# GEARDRONE_F4_4.net
KiCad netlist of a schematic drawn in Altium Designer
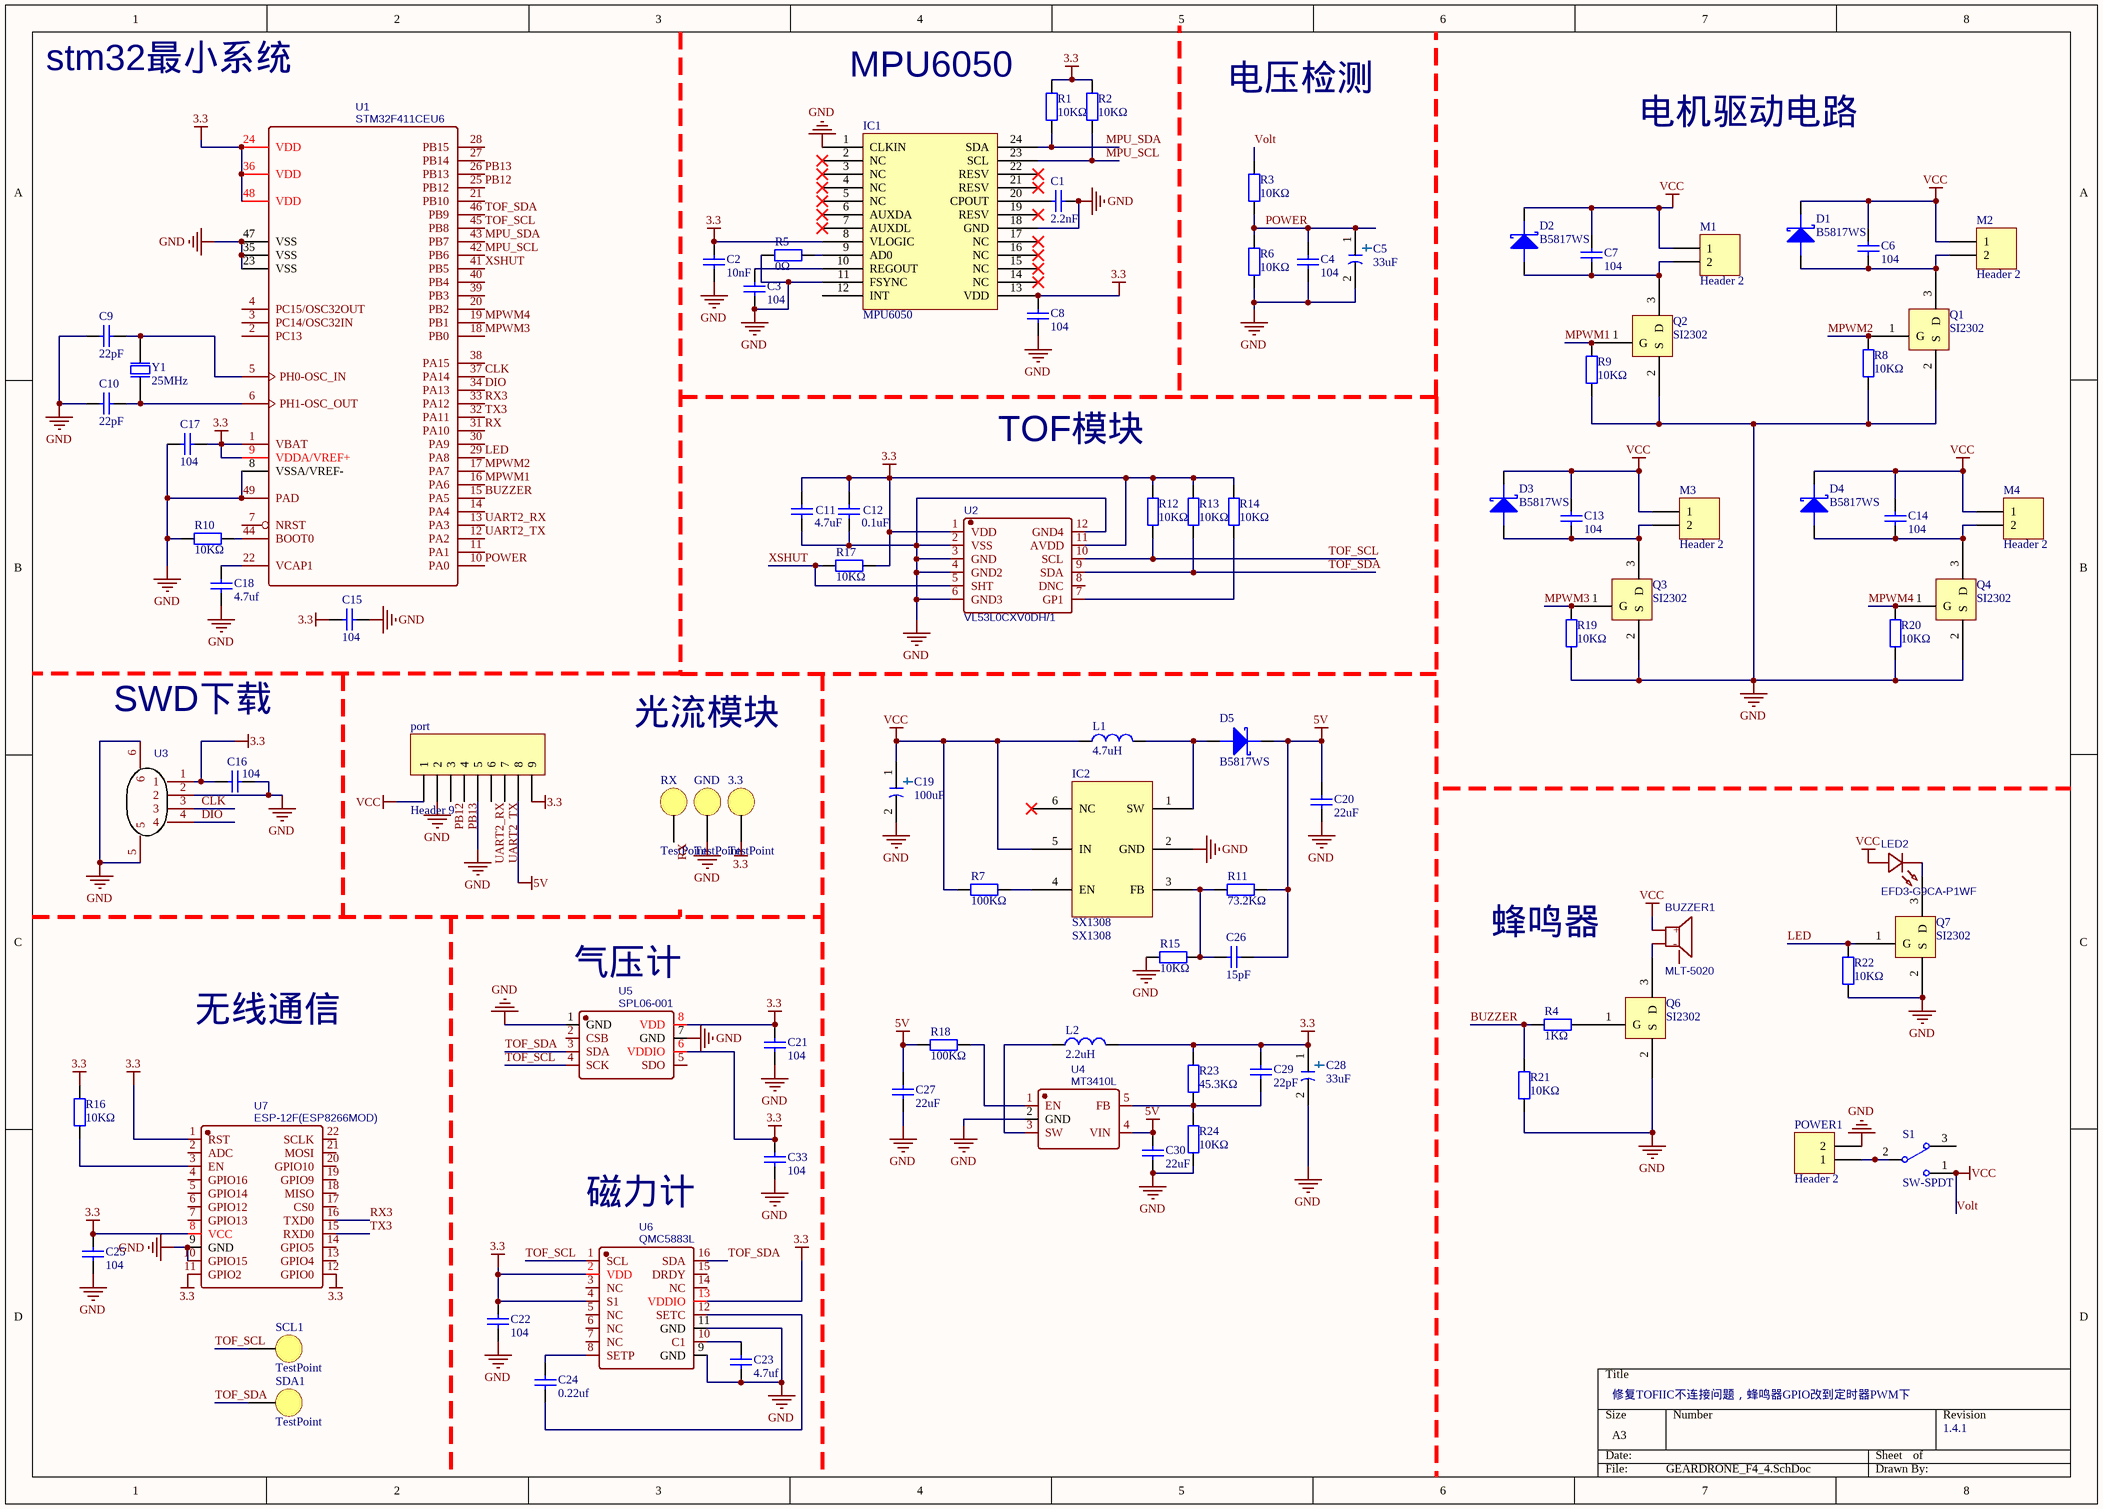
[diagram p0: GEARDRONE_F4_4.SchDoc]

(export (version "E")
  (design (tool "Eeschema 10.0.6"))
  (components
    (comp (ref "3.3")
      (value "TestPoint")
      (footprint "TestPoint")
      (libsource (lib "CQL_SchLib") (part "TestPoint"))
    )
    (comp (ref "BUZZER1")
      (value "MLT-5020")
      (footprint "BUZ-SMD_3P-L5.2-W5.2-P3.50-BR")
      (fields (field (name "BOM_SUPPLIER PART") "C94598"))
      (libsource (lib "Y1") (part "MLT-5020"))
    )
    (comp (ref "C1")
      (value "2.2nF")
      (footprint "0603_C")
      (description "Polarized Capacitor (Radial)")
      (fields (field (name "Comment") "2.2nf") (field (name "PUBLISHER") "Altium Limited"))
      (libsource (lib "电容") (part "Cap Chip 0603"))
    )
    (comp (ref "C2")
      (value "10nF")
      (footprint "0603_C")
      (description "Polarized Capacitor (Radial)")
      (fields (field (name "Comment") "10nf") (field (name "PUBLISHER") "Altium Limited"))
      (libsource (lib "电容") (part "Cap Chip 0603"))
    )
    (comp (ref "C3")
      (value "104")
      (footprint "0603_C")
      (description "Polarized Capacitor (Radial)")
      (fields (field (name "PUBLISHER") "Altium Limited"))
      (libsource (lib "电容") (part "Cap Chip 0603"))
    )
    (comp (ref "C4")
      (value "104")
      (footprint "0603_C")
      (description "Polarized Capacitor (Radial)")
      (fields (field (name "PUBLISHER") "Altium Limited"))
      (libsource (lib "电容") (part "Cap Chip 0603"))
    )
    (comp (ref "C5")
      (value "33uf")
      (footprint "CASE-B_3528")
      (fields (field (name "ALTIUM_UNNAMED_1") "33uF"))
      (libsource (lib "mySchlib") (part "ECAP"))
    )
    (comp (ref "C6")
      (value "104")
      (footprint "0603_C")
      (description "Polarized Capacitor (Radial)")
      (fields (field (name "PUBLISHER") "Altium Limited"))
      (libsource (lib "电容") (part "Cap Chip 0603"))
    )
    (comp (ref "C7")
      (value "104")
      (footprint "0603_C")
      (description "Polarized Capacitor (Radial)")
      (fields (field (name "PUBLISHER") "Altium Limited"))
      (libsource (lib "电容") (part "Cap Chip 0603"))
    )
    (comp (ref "C8")
      (value "104")
      (footprint "0603_C")
      (description "Polarized Capacitor (Radial)")
      (fields (field (name "PUBLISHER") "Altium Limited"))
      (libsource (lib "电容") (part "Cap Chip 0603"))
    )
    (comp (ref "C9")
      (value "22pF")
      (footprint "0603_C")
      (description "Polarized Capacitor (Radial)")
      (fields (field (name "Comment") "22pf") (field (name "PUBLISHER") "Altium Limited"))
      (libsource (lib "电容") (part "Cap Chip 0805"))
    )
    (comp (ref "C10")
      (value "22pF")
      (footprint "0603_C")
      (description "Polarized Capacitor (Radial)")
      (fields (field (name "Comment") "22pf") (field (name "PUBLISHER") "Altium Limited"))
      (libsource (lib "电容") (part "Cap Chip 0805"))
    )
    (comp (ref "C11")
      (value "4.7uF")
      (footprint "0603_C")
      (description "Polarized Capacitor (Radial)")
      (fields (field (name "Comment") "4.7uf") (field (name "PUBLISHER") "Altium Limited"))
      (libsource (lib "电容") (part "Cap Chip 0603"))
    )
    (comp (ref "C12")
      (value "0.1uF")
      (footprint "0603_C")
      (description "Polarized Capacitor (Radial)")
      (fields (field (name "Comment") "0.1uf") (field (name "PUBLISHER") "Altium Limited"))
      (libsource (lib "电容") (part "Cap Chip 0603"))
    )
    (comp (ref "C13")
      (value "104")
      (footprint "0603_C")
      (description "Polarized Capacitor (Radial)")
      (fields (field (name "PUBLISHER") "Altium Limited"))
      (libsource (lib "电容") (part "Cap Chip 0603"))
    )
    (comp (ref "C14")
      (value "104")
      (footprint "0603_C")
      (description "Polarized Capacitor (Radial)")
      (fields (field (name "PUBLISHER") "Altium Limited"))
      (libsource (lib "电容") (part "Cap Chip 0603"))
    )
    (comp (ref "C15")
      (value "104")
      (footprint "0603_C")
      (description "Polarized Capacitor (Radial)")
      (fields (field (name "PUBLISHER") "Altium Limited"))
      (libsource (lib "电容") (part "Cap Chip 0603"))
    )
    (comp (ref "C16")
      (value "104")
      (footprint "0603_C")
      (description "Polarized Capacitor (Radial)")
      (fields (field (name "PUBLISHER") "Altium Limited"))
      (libsource (lib "电容") (part "Cap Chip 0603"))
    )
    (comp (ref "C17")
      (value "104")
      (footprint "0603_C")
      (description "Polarized Capacitor (Radial)")
      (fields (field (name "PUBLISHER") "Altium Limited"))
      (libsource (lib "电容") (part "Cap Chip 0603"))
    )
    (comp (ref "C18")
      (value "4.7uf")
      (footprint "0603_C")
      (description "Polarized Capacitor (Radial)")
      (fields (field (name "PUBLISHER") "Altium Limited"))
      (libsource (lib "电容") (part "Cap Chip 0603"))
    )
    (comp (ref "C19")
      (value "100uf")
      (footprint "CASE-B_3528")
      (fields (field (name "ALTIUM_UNNAMED_1") "100uF"))
      (libsource (lib "mySchlib") (part "ECAP"))
    )
    (comp (ref "C20")
      (value "22uF")
      (footprint "0603_C")
      (description "Polarized Capacitor (Radial)")
      (fields (field (name "Comment") "22uf") (field (name "PUBLISHER") "Altium Limited"))
      (libsource (lib "电容") (part "Cap Chip 0603"))
    )
    (comp (ref "C21")
      (value "104")
      (footprint "0603_C")
      (description "Polarized Capacitor (Radial)")
      (fields (field (name "PUBLISHER") "Altium Limited"))
      (libsource (lib "电容") (part "Cap Chip 0603"))
    )
    (comp (ref "C22")
      (value "104")
      (footprint "0603_C")
      (description "Polarized Capacitor (Radial)")
      (fields (field (name "PUBLISHER") "Altium Limited"))
      (libsource (lib "电容") (part "Cap Chip 0603"))
    )
    (comp (ref "C23")
      (value "4.7uf")
      (footprint "0603_C")
      (description "Polarized Capacitor (Radial)")
      (fields (field (name "PUBLISHER") "Altium Limited"))
      (libsource (lib "电容") (part "Cap Chip 0603"))
    )
    (comp (ref "C24")
      (value "0.22uf")
      (footprint "0603_C")
      (description "Polarized Capacitor (Radial)")
      (fields (field (name "PUBLISHER") "Altium Limited"))
      (libsource (lib "电容") (part "Cap Chip 0603"))
    )
    (comp (ref "C25")
      (value "104")
      (footprint "0603_C")
      (description "Polarized Capacitor (Radial)")
      (fields (field (name "PUBLISHER") "Altium Limited"))
      (libsource (lib "电容") (part "Cap Chip 0603"))
    )
    (comp (ref "C26")
      (value "15pF")
      (footprint "0603_C")
      (description "Polarized Capacitor (Radial)")
      (fields (field (name "Comment") "15pf") (field (name "PUBLISHER") "Altium Limited"))
      (libsource (lib "电容") (part "Cap Chip 0603"))
    )
    (comp (ref "C27")
      (value "22uF")
      (footprint "0603_C")
      (description "Polarized Capacitor (Radial)")
      (fields (field (name "PUBLISHER") "Altium Limited"))
      (libsource (lib "电容") (part "Cap Chip 0603"))
    )
    (comp (ref "C28")
      (value "33uf")
      (footprint "CASE-B_3528")
      (fields (field (name "ALTIUM_UNNAMED_1") "33uF"))
      (libsource (lib "mySchlib") (part "ECAP"))
    )
    (comp (ref "C29")
      (value "22pF")
      (footprint "0603_C")
      (description "Polarized Capacitor (Radial)")
      (fields (field (name "PUBLISHER") "Altium Limited"))
      (libsource (lib "电容") (part "Cap Chip 0603"))
    )
    (comp (ref "C30")
      (value "22uF")
      (footprint "0603_C")
      (description "Polarized Capacitor (Radial)")
      (fields (field (name "PUBLISHER") "Altium Limited"))
      (libsource (lib "电容") (part "Cap Chip 0603"))
    )
    (comp (ref "C33")
      (value "104")
      (footprint "0603_C")
      (description "Polarized Capacitor (Radial)")
      (fields (field (name "PUBLISHER") "Altium Limited"))
      (libsource (lib "电容") (part "Cap Chip 0603"))
    )
    (comp (ref "D1")
      (value "B5817WS")
      (footprint "SOD-323")
      (libsource (lib "二极管 三极管 MOS") (part "DIODE-TVS"))
    )
    (comp (ref "D2")
      (value "B5817WS")
      (footprint "SOD-323")
      (libsource (lib "二极管 三极管 MOS") (part "DIODE-TVS"))
    )
    (comp (ref "D3")
      (value "B5817WS")
      (footprint "SOD-323")
      (libsource (lib "二极管 三极管 MOS") (part "DIODE-TVS"))
    )
    (comp (ref "D4")
      (value "B5817WS")
      (footprint "SOD-323")
      (libsource (lib "二极管 三极管 MOS") (part "DIODE-TVS"))
    )
    (comp (ref "D5")
      (value "B5817WS")
      (footprint "SOD-323")
      (libsource (lib "二极管 三极管 MOS") (part "DIODE-TVS"))
    )
    (comp (ref "GND")
      (value "TestPoint")
      (footprint "TestPoint")
      (libsource (lib "CQL_SchLib") (part "TestPoint"))
    )
    (comp (ref "IC1")
      (value "MPU6050")
      (footprint "LC-QFN-24_4x4x05P")
      (description "三轴陀螺仪")
      (libsource (lib "模块") (part "MPU6050"))
    )
    (comp (ref "IC2") (value "SX1308") (footprint "LC-SOT-23-6") (libsource (lib "Schlib1") (part "SX1308")))
    (comp (ref "L1")
      (value "4.7uH")
      (footprint "CD43NP")
      (description "Inductor")
      (fields (field (name "PUBLISHER") "Altium Limited"))
      (libsource (lib "电感磁珠共轭圈") (part "Inductor Chip"))
    )
    (comp (ref "L2")
      (value "2.2uH")
      (footprint "IND-SMD_L3.0-W3.0")
      (description "Inductor")
      (fields (field (name "PUBLISHER") "Altium Limited"))
      (libsource (lib "电感磁珠共轭圈") (part "Inductor Chip"))
    )
    (comp (ref "LED2")
      (value "EFD3-G9CA-P1WF")
      (footprint "LED3528")
      (fields (field (name "BOM_SUPPLIER PART") "C507038") (field (name "CONTRIBUTOR") "LCSC"))
      (libsource (lib "altium-import") (part "root_2_EFD3-G9CA-P1WF_"))
    )
    (comp (ref "M1")
      (value "Header 2")
      (footprint "HDR1X2")
      (description "Header, 2-Pin")
      (fields (field (name "PUBLISHER") "Altium Limited"))
      (libsource (lib "The BeatlesIntegratedLibrary") (part "Header 2"))
    )
    (comp (ref "M2")
      (value "Header 2")
      (footprint "HDR1X2")
      (description "Header, 2-Pin")
      (fields (field (name "PUBLISHER") "Altium Limited"))
      (libsource (lib "The BeatlesIntegratedLibrary") (part "Header 2"))
    )
    (comp (ref "M3")
      (value "Header 2")
      (footprint "HDR1X2")
      (description "Header, 2-Pin")
      (fields (field (name "PUBLISHER") "Altium Limited"))
      (libsource (lib "The BeatlesIntegratedLibrary") (part "Header 2"))
    )
    (comp (ref "M4")
      (value "Header 2")
      (footprint "HDR1X2")
      (description "Header, 2-Pin")
      (fields (field (name "PUBLISHER") "Altium Limited"))
      (libsource (lib "The BeatlesIntegratedLibrary") (part "Header 2"))
    )
    (comp (ref "port")
      (value "Header 9")
      (footprint "HDR1X9")
      (description "Header, 9-Pin")
      (fields (field (name "PUBLISHER") "Altium Limited"))
      (libsource (lib "Miscellaneous Connectors") (part "Header 9"))
    )
    (comp (ref "POWER1")
      (value "Header 2")
      (footprint "HDR1X2")
      (description "Header, 2-Pin")
      (fields (field (name "PUBLISHER") "Altium Limited"))
      (libsource (lib "") (part "Header 2_1"))
    )
    (comp (ref "Q1")
      (value "SI2302")
      (footprint "LC-SOT-23(SOT-23-3)")
      (libsource (lib "SI2302") (part "HANDSOME-SI2302-N"))
    )
    (comp (ref "Q2")
      (value "SI2302")
      (footprint "LC-SOT-23(SOT-23-3)")
      (libsource (lib "SI2302") (part "HANDSOME-SI2302-N"))
    )
    (comp (ref "Q3")
      (value "SI2302")
      (footprint "LC-SOT-23(SOT-23-3)")
      (libsource (lib "SI2302") (part "HANDSOME-SI2302-N"))
    )
    (comp (ref "Q4")
      (value "SI2302")
      (footprint "LC-SOT-23(SOT-23-3)")
      (libsource (lib "SI2302") (part "HANDSOME-SI2302-N"))
    )
    (comp (ref "Q6")
      (value "SI2302")
      (footprint "LC-SOT-23(SOT-23-3)")
      (libsource (lib "SI2302") (part "HANDSOME-SI2302-N"))
    )
    (comp (ref "Q7")
      (value "SI2302")
      (footprint "LC-SOT-23(SOT-23-3)")
      (libsource (lib "SI2302") (part "HANDSOME-SI2302-N"))
    )
    (comp (ref "R1")
      (value "10KΩ")
      (footprint "0603_R")
      (description "Resistor")
      (fields (field (name "Comment") "10k") (field (name "PUBLISHER") "Altium Limited"))
      (libsource (lib "电阻") (part "Resistor Chip 0805"))
    )
    (comp (ref "R2")
      (value "10KΩ")
      (footprint "0603_R")
      (description "Resistor")
      (fields (field (name "Comment") "10k") (field (name "PUBLISHER") "Altium Limited"))
      (libsource (lib "电阻") (part "Resistor Chip 0805"))
    )
    (comp (ref "R3")
      (value "10KΩ")
      (footprint "0603_R")
      (description "Resistor")
      (fields (field (name "Comment") "10k") (field (name "PUBLISHER") "Altium Limited"))
      (libsource (lib "电阻") (part "Resistor Chip 0805"))
    )
    (comp (ref "R4")
      (value "1KΩ")
      (footprint "0603_R")
      (description "Resistor")
      (fields (field (name "Comment") "1k") (field (name "PUBLISHER") "Altium Limited"))
      (libsource (lib "") (part "Resistor Chip 0805_3"))
    )
    (comp (ref "R5")
      (value "0Ω")
      (footprint "0603_R")
      (description "Resistor")
      (fields (field (name "Comment") "0") (field (name "PUBLISHER") "Altium Limited"))
      (libsource (lib "") (part "Resistor Chip 0805_1"))
    )
    (comp (ref "R6")
      (value "10KΩ")
      (footprint "0603_R")
      (description "Resistor")
      (fields (field (name "Comment") "10k") (field (name "PUBLISHER") "Altium Limited"))
      (libsource (lib "电阻") (part "Resistor Chip 0805"))
    )
    (comp (ref "R7")
      (value "100KΩ")
      (footprint "0603_R")
      (description "Resistor")
      (fields (field (name "Comment") "100k") (field (name "PUBLISHER") "Altium Limited"))
      (libsource (lib "") (part "Resistor Chip 0805_1"))
    )
    (comp (ref "R8")
      (value "10KΩ")
      (footprint "0603_R")
      (description "Resistor")
      (fields (field (name "Comment") "10k") (field (name "PUBLISHER") "Altium Limited"))
      (libsource (lib "电阻") (part "Resistor Chip 0805"))
    )
    (comp (ref "R9")
      (value "10KΩ")
      (footprint "0603_R")
      (description "Resistor")
      (fields (field (name "Comment") "10k") (field (name "PUBLISHER") "Altium Limited"))
      (libsource (lib "") (part "Resistor Chip 0805_2"))
    )
    (comp (ref "R10")
      (value "10KΩ")
      (footprint "0603_R")
      (description "Resistor")
      (fields (field (name "Comment") "10kΩ") (field (name "PUBLISHER") "Altium Limited"))
      (libsource (lib "") (part "Resistor Chip 0805_1"))
    )
    (comp (ref "R11")
      (value "73.2KΩ")
      (footprint "0603_R")
      (description "Resistor")
      (fields (field (name "Comment") "73.2k") (field (name "PUBLISHER") "Altium Limited"))
      (libsource (lib "") (part "Resistor Chip 0805_1"))
    )
    (comp (ref "R12")
      (value "10KΩ")
      (footprint "0603_R")
      (description "Resistor")
      (fields (field (name "Comment") "10k") (field (name "PUBLISHER") "Altium Limited"))
      (libsource (lib "电阻") (part "Resistor Chip 0805"))
    )
    (comp (ref "R13")
      (value "10KΩ")
      (footprint "0603_R")
      (description "Resistor")
      (fields (field (name "Comment") "10k") (field (name "PUBLISHER") "Altium Limited"))
      (libsource (lib "电阻") (part "Resistor Chip 0805"))
    )
    (comp (ref "R14")
      (value "10KΩ")
      (footprint "0603_R")
      (description "Resistor")
      (fields (field (name "Comment") "10k") (field (name "PUBLISHER") "Altium Limited"))
      (libsource (lib "电阻") (part "Resistor Chip 0805"))
    )
    (comp (ref "R15")
      (value "10KΩ")
      (footprint "0603_R")
      (description "Resistor")
      (fields (field (name "Comment") "10k") (field (name "PUBLISHER") "Altium Limited"))
      (libsource (lib "") (part "Resistor Chip 0805_3"))
    )
    (comp (ref "R16")
      (value "10KΩ")
      (footprint "0603_R")
      (description "Resistor")
      (fields (field (name "Comment") "10k") (field (name "PUBLISHER") "Altium Limited"))
      (libsource (lib "电阻") (part "Resistor Chip 0805"))
    )
    (comp (ref "R17")
      (value "10KΩ")
      (footprint "0603_R")
      (description "Resistor")
      (fields (field (name "Comment") "10k") (field (name "PUBLISHER") "Altium Limited"))
      (libsource (lib "") (part "Resistor Chip 0805_1"))
    )
    (comp (ref "R18")
      (value "100KΩ")
      (footprint "0603_R")
      (description "Resistor")
      (fields (field (name "Comment") "100k") (field (name "PUBLISHER") "Altium Limited"))
      (libsource (lib "") (part "Resistor Chip 0805_1"))
    )
    (comp (ref "R19")
      (value "10KΩ")
      (footprint "0603_R")
      (description "Resistor")
      (fields (field (name "Comment") "10k") (field (name "PUBLISHER") "Altium Limited"))
      (libsource (lib "电阻") (part "Resistor Chip 0805"))
    )
    (comp (ref "R20")
      (value "10KΩ")
      (footprint "0603_R")
      (description "Resistor")
      (fields (field (name "Comment") "10k") (field (name "PUBLISHER") "Altium Limited"))
      (libsource (lib "电阻") (part "Resistor Chip 0805"))
    )
    (comp (ref "R21")
      (value "10KΩ")
      (footprint "0603_R")
      (description "Resistor")
      (fields (field (name "Comment") "10k") (field (name "PUBLISHER") "Altium Limited"))
      (libsource (lib "") (part "Resistor Chip 0805_2"))
    )
    (comp (ref "R22")
      (value "10KΩ")
      (footprint "0603_R")
      (description "Resistor")
      (fields (field (name "Comment") "10k") (field (name "PUBLISHER") "Altium Limited"))
      (libsource (lib "") (part "Resistor Chip 0805_2"))
    )
    (comp (ref "R23")
      (value "45.3KΩ")
      (footprint "0603_R")
      (description "Resistor")
      (fields (field (name "PUBLISHER") "Altium Limited"))
      (libsource (lib "") (part "Resistor Chip 0805_2"))
    )
    (comp (ref "R24")
      (value "10KΩ")
      (footprint "0603_R")
      (description "Resistor")
      (fields (field (name "PUBLISHER") "Altium Limited"))
      (libsource (lib "") (part "Resistor Chip 0805_2"))
    )
    (comp (ref "RX")
      (value "TestPoint")
      (footprint "TestPoint")
      (libsource (lib "CQL_SchLib") (part "TestPoint"))
    )
    (comp (ref "S1")
      (value "SW-SPDT")
      (footprint "8.5*3.5_3P")
      (description "SPDT Subminiature Toggle Switch, Right Angle Mounting, Vertical Actuation")
      (fields (field (name "PUBLISHER") "Altium Limited"))
      (libsource (lib "开关按键器件") (part "SW-SPDT"))
    )
    (comp (ref "SCL1")
      (value "TestPoint")
      (footprint "TestPoint")
      (libsource (lib "CQL_SchLib") (part "TestPoint"))
    )
    (comp (ref "SDA1")
      (value "TestPoint")
      (footprint "TestPoint")
      (libsource (lib "CQL_SchLib") (part "TestPoint"))
    )
    (comp (ref "U1")
      (value "STM32F411CEU6")
      (footprint "UFQFPN-48_L7.0-W7.0-P0.50-BL-EP")
      (fields (field (name "BOM_SUPPLIER PART") "C60420"))
      (libsource (lib "altium-import") (part "root_0_STM32F411CEU6_"))
    )
    (comp (ref "U2")
      (value "VL53L0CXV0DH/1")
      (footprint "OPTO-SMD_12P_VL53L0CXV0DH-1")
      (fields (field (name "BOM_SUPPLIER PART") "C91199"))
      (libsource (lib "Y1") (part "VL53L0CXV0DH/1"))
    )
    (comp (ref "U3")
      (value "SM04B-GHS-TB(LF)(SN)")
      (footprint "CONN-SMD_4P-P1.25_SM04B-GHS-TB-LF-SN")
      (fields (field (name "BOM_SUPPLIER PART") "C189895") (field (name "CONTRIBUTOR") "LCSC"))
      (libsource (lib "Y1") (part "SM04B-GHS-TB(LF)(SN)"))
    )
    (comp (ref "U4")
      (value "MT3410L")
      (footprint "SOT-23-5_L2.9-W1.6-P0.95-LS2.8-BL")
      (fields (field (name "BOM_SUPPLIER PART") "C83223"))
      (libsource (lib "altium-import") (part "root_0_MT3410L_"))
    )
    (comp (ref "U5")
      (value "SPL06-001")
      (footprint "SENSOR-SMD_SPL06-001")
      (fields (field (name "BOM_SUPPLIER PART") "C2684428") (field (name "CONTRIBUTOR") "LCSC"))
      (libsource (lib "altium-import") (part "root_0_SPL06-001_"))
    )
    (comp (ref "U6")
      (value "QMC5883L")
      (footprint "LPCC-16_L3.0-W3.0-P0.50-BL")
      (fields
        (field (name "BOM_SUPPLIER PART") "C2859540")
        (field (name "BOM_MANUFACTURER PART") "HMC5883L")
        (field (name "CONTRIBUTOR") "LCSC")
      )
      (libsource (lib "altium-import") (part "root_0_HMC5883L_"))
    )
    (comp (ref "U7")
      (value "ESP-12F(ESP8266MOD)")
      (footprint "WIFIM-SMD_ESP-12F-ESP8266MOD")
      (fields (field (name "BOM_SUPPLIER PART") "C82891"))
      (libsource (lib "altium-import") (part "root_0_ESP-12F(ESP8266MOD)_"))
    )
    (comp (ref "Y1")
      (value "25MHZ 5032")
      (footprint "SMD-5032_2P")
      (description "Crystal Oscillator")
      (fields (field (name "FREQUENCY") "25MHz") (field (name "PUBLISHER") "Altium Limited"))
      (libsource (lib "蜂鸣器 咪头 保险丝 电池 晶振") (part "XTAL"))
    )
  )
  (nets
    (net (code "1") (name "/BUZZER") (class "Default")
      (node (ref "R21") (pin "2") (pinfunction "2_2") (pintype "passive"))
      (node (ref "R4") (pin "2") (pinfunction "2_2") (pintype "passive"))
      (node (ref "U1") (pin "15") (pinfunction "PA5_15") (pintype "passive"))
    )
    (net (code "2") (name "/CLK") (class "Default")
      (node (ref "U1") (pin "37") (pinfunction "PA14_37") (pintype "passive"))
      (node (ref "U3") (pin "3") (pinfunction "3_3") (pintype "passive"))
    )
    (net (code "3") (name "/DIO") (class "Default")
      (node (ref "U1") (pin "34") (pinfunction "PA13_34") (pintype "passive"))
      (node (ref "U3") (pin "4") (pinfunction "4_4") (pintype "passive"))
    )
    (net (code "4") (name "/LED") (class "Default")
      (node (ref "Q7") (pin "1") (pinfunction "G_1") (pintype "passive"))
      (node (ref "R22") (pin "2") (pinfunction "2_2") (pintype "passive"))
      (node (ref "U1") (pin "29") (pinfunction "PA8_29") (pintype "passive"))
    )
    (net (code "5") (name "/MPU_SCL") (class "Default")
      (node (ref "IC1") (pin "23") (pinfunction "SCL_23") (pintype "passive"))
      (node (ref "R2") (pin "2") (pinfunction "2_2") (pintype "passive"))
      (node (ref "U1") (pin "42") (pinfunction "PB6_42") (pintype "passive"))
    )
    (net (code "6") (name "/MPU_SDA") (class "Default")
      (node (ref "IC1") (pin "24") (pinfunction "SDA_24") (pintype "passive"))
      (node (ref "R1") (pin "2") (pinfunction "2_2") (pintype "passive"))
      (node (ref "U1") (pin "43") (pinfunction "PB7_43") (pintype "passive"))
    )
    (net (code "7") (name "/MPWM1") (class "Default")
      (node (ref "Q2") (pin "1") (pinfunction "G_1") (pintype "passive"))
      (node (ref "R9") (pin "2") (pinfunction "2_2") (pintype "passive"))
      (node (ref "U1") (pin "16") (pinfunction "PA6_16") (pintype "passive"))
    )
    (net (code "8") (name "/MPWM2") (class "Default")
      (node (ref "Q1") (pin "1") (pinfunction "G_1") (pintype "passive"))
      (node (ref "R8") (pin "1") (pinfunction "1_1") (pintype "passive"))
      (node (ref "U1") (pin "17") (pinfunction "PA7_17") (pintype "passive"))
    )
    (net (code "9") (name "/MPWM3") (class "Default")
      (node (ref "Q3") (pin "1") (pinfunction "G_1") (pintype "passive"))
      (node (ref "R19") (pin "1") (pinfunction "1_1") (pintype "passive"))
      (node (ref "U1") (pin "18") (pinfunction "PB0_18") (pintype "passive"))
    )
    (net (code "10") (name "/MPWM4") (class "Default")
      (node (ref "Q4") (pin "1") (pinfunction "G_1") (pintype "passive"))
      (node (ref "R20") (pin "1") (pinfunction "1_1") (pintype "passive"))
      (node (ref "U1") (pin "19") (pinfunction "PB1_19") (pintype "passive"))
    )
    (net (code "11") (name "/PB12") (class "Default")
      (node (ref "U1") (pin "25") (pinfunction "PB12_25") (pintype "passive"))
      (node (ref "port") (pin "3") (pinfunction "3_3") (pintype "passive"))
    )
    (net (code "12") (name "/PB13") (class "Default")
      (node (ref "U1") (pin "26") (pinfunction "PB13_26") (pintype "passive"))
      (node (ref "port") (pin "4") (pinfunction "4_4") (pintype "passive"))
    )
    (net (code "13") (name "/POWER") (class "Default")
      (node (ref "C4") (pin "1") (pinfunction "1_1") (pintype "passive"))
      (node (ref "C5") (pin "1") (pinfunction "1_1") (pintype "passive"))
      (node (ref "R3") (pin "2") (pinfunction "2_2") (pintype "passive"))
      (node (ref "R6") (pin "1") (pinfunction "1_1") (pintype "passive"))
      (node (ref "U1") (pin "10") (pinfunction "PA0_10") (pintype "passive"))
    )
    (net (code "14") (name "/RX") (class "Default")
      (node (ref "RX") (pin "1") (pinfunction "TestPoint_1") (pintype "passive"))
      (node (ref "U1") (pin "31") (pinfunction "PA10_31") (pintype "passive"))
    )
    (net (code "15") (name "/RX3") (class "Default")
      (node (ref "U1") (pin "33") (pinfunction "PA12_33") (pintype "passive"))
      (node (ref "U7") (pin "16") (pinfunction "TXD0_16") (pintype "passive"))
    )
    (net (code "16") (name "/TOF_SCL") (class "Default")
      (node (ref "R12") (pin "2") (pinfunction "2_2") (pintype "passive"))
      (node (ref "SCL1") (pin "1") (pinfunction "TestPoint_1") (pintype "passive"))
      (node (ref "U1") (pin "45") (pinfunction "PB8_45") (pintype "passive"))
      (node (ref "U2") (pin "10") (pinfunction "SCL_10") (pintype "passive"))
      (node (ref "U5") (pin "4") (pinfunction "SCK_4") (pintype "passive"))
      (node (ref "U6") (pin "1") (pinfunction "SCL_1") (pintype "passive"))
    )
    (net (code "17") (name "/TOF_SDA") (class "Default")
      (node (ref "R13") (pin "2") (pinfunction "2_2") (pintype "passive"))
      (node (ref "SDA1") (pin "1") (pinfunction "TestPoint_1") (pintype "passive"))
      (node (ref "U1") (pin "46") (pinfunction "PB9_46") (pintype "passive"))
      (node (ref "U2") (pin "9") (pinfunction "SDA_9") (pintype "passive"))
      (node (ref "U5") (pin "3") (pinfunction "SDA_3") (pintype "passive"))
      (node (ref "U6") (pin "16") (pinfunction "SDA_16") (pintype "passive"))
    )
    (net (code "18") (name "/TX3") (class "Default")
      (node (ref "U1") (pin "32") (pinfunction "PA11_32") (pintype "passive"))
      (node (ref "U7") (pin "15") (pinfunction "RXD0_15") (pintype "passive"))
    )
    (net (code "19") (name "/UART2_RX") (class "Default")
      (node (ref "U1") (pin "13") (pinfunction "PA3_13") (pintype "passive"))
      (node (ref "port") (pin "6") (pinfunction "6_6") (pintype "passive"))
    )
    (net (code "20") (name "/UART2_TX") (class "Default")
      (node (ref "U1") (pin "12") (pinfunction "PA2_12") (pintype "passive"))
      (node (ref "port") (pin "7") (pinfunction "7_7") (pintype "passive"))
    )
    (net (code "21") (name "/XSHUT") (class "Default")
      (node (ref "R17") (pin "1") (pinfunction "1_1") (pintype "passive"))
      (node (ref "U1") (pin "41") (pinfunction "PB5_41") (pintype "passive"))
      (node (ref "U2") (pin "5") (pinfunction "SHT_5") (pintype "passive"))
    )
    (net (code "22") (name "3.3") (class "Default")
      (node (ref "3.3") (pin "1") (pinfunction "TestPoint_1") (pintype "passive"))
      (node (ref "C11") (pin "2") (pinfunction "2_2") (pintype "passive"))
      (node (ref "C12") (pin "2") (pinfunction "2_2") (pintype "passive"))
      (node (ref "C15") (pin "2") (pinfunction "2_2") (pintype "passive"))
      (node (ref "C16") (pin "2") (pinfunction "2_2") (pintype "passive"))
      (node (ref "C17") (pin "1") (pinfunction "1_1") (pintype "passive"))
      (node (ref "C2") (pin "2") (pinfunction "2_2") (pintype "passive"))
      (node (ref "C21") (pin "1") (pinfunction "1_1") (pintype "passive"))
      (node (ref "C22") (pin "1") (pinfunction "1_1") (pintype "passive"))
      (node (ref "C25") (pin "1") (pinfunction "1_1") (pintype "passive"))
      (node (ref "C28") (pin "1") (pinfunction "1_1") (pintype "passive"))
      (node (ref "C29") (pin "1") (pinfunction "1_1") (pintype "passive"))
      (node (ref "C33") (pin "1") (pinfunction "1_1") (pintype "passive"))
      (node (ref "C8") (pin "1") (pinfunction "1_1") (pintype "passive"))
      (node (ref "IC1") (pin "13") (pinfunction "VDD_13") (pintype "passive"))
      (node (ref "IC1") (pin "8") (pinfunction "VLOGIC_8") (pintype "passive"))
      (node (ref "L2") (pin "2") (pinfunction "2_2") (pintype "passive"))
      (node (ref "R1") (pin "1") (pinfunction "1_1") (pintype "passive"))
      (node (ref "R12") (pin "1") (pinfunction "1_1") (pintype "passive"))
      (node (ref "R13") (pin "1") (pinfunction "1_1") (pintype "passive"))
      (node (ref "R14") (pin "1") (pinfunction "1_1") (pintype "passive"))
      (node (ref "R16") (pin "1") (pinfunction "1_1") (pintype "passive"))
      (node (ref "R17") (pin "2") (pinfunction "2_2") (pintype "passive"))
      (node (ref "R2") (pin "1") (pinfunction "1_1") (pintype "passive"))
      (node (ref "R23") (pin "2") (pinfunction "2_2") (pintype "passive"))
      (node (ref "U1") (pin "1") (pinfunction "VBAT_1") (pintype "passive"))
      (node (ref "U1") (pin "24") (pinfunction "VDD_24") (pintype "passive"))
      (node (ref "U1") (pin "36") (pinfunction "VDD_36") (pintype "passive"))
      (node (ref "U1") (pin "48") (pinfunction "VDD_48") (pintype "passive"))
      (node (ref "U1") (pin "9") (pinfunction "VDDA/VREF+_9") (pintype "passive"))
      (node (ref "U2") (pin "1") (pinfunction "VDD_1") (pintype "passive"))
      (node (ref "U2") (pin "11") (pinfunction "AVDD_11") (pintype "passive"))
      (node (ref "U3") (pin "1") (pinfunction "1_1") (pintype "passive"))
      (node (ref "U5") (pin "6") (pinfunction "VDDIO_6") (pintype "passive"))
      (node (ref "U5") (pin "8") (pinfunction "VDD_8") (pintype "passive"))
      (node (ref "U6") (pin "13") (pinfunction "VDDIO_13") (pintype "passive"))
      (node (ref "U6") (pin "2") (pinfunction "VDD_2") (pintype "passive"))
      (node (ref "U6") (pin "4") (pinfunction "S1_4") (pintype "passive"))
      (node (ref "U7") (pin "1") (pinfunction "RST_1") (pintype "passive"))
      (node (ref "U7") (pin "11") (pinfunction "GPIO2_11") (pintype "passive"))
      (node (ref "U7") (pin "12") (pinfunction "GPIO0_12") (pintype "passive"))
      (node (ref "U7") (pin "8") (pinfunction "VCC_8") (pintype "passive"))
      (node (ref "port") (pin "9") (pinfunction "9_9") (pintype "passive"))
    )
    (net (code "23") (name "5V") (class "Default")
      (node (ref "C20") (pin "2") (pinfunction "2_2") (pintype "passive"))
      (node (ref "C26") (pin "1") (pinfunction "1_1") (pintype "passive"))
      (node (ref "C27") (pin "2") (pinfunction "2_2") (pintype "passive"))
      (node (ref "C30") (pin "2") (pinfunction "2_2") (pintype "passive"))
      (node (ref "D5") (pin "2") (pinfunction "K_2") (pintype "passive"))
      (node (ref "R11") (pin "2") (pinfunction "2_2") (pintype "passive"))
      (node (ref "R18") (pin "1") (pinfunction "1_1") (pintype "passive"))
      (node (ref "U4") (pin "4") (pinfunction "VIN_4") (pintype "passive"))
      (node (ref "port") (pin "8") (pinfunction "8_8") (pintype "passive"))
    )
    (net (code "24") (name "GND") (class "Default")
      (node (ref "C1") (pin "2") (pinfunction "2_2") (pintype "passive"))
      (node (ref "C10") (pin "1") (pinfunction "1_1") (pintype "passive"))
      (node (ref "C11") (pin "1") (pinfunction "1_1") (pintype "passive"))
      (node (ref "C12") (pin "1") (pinfunction "1_1") (pintype "passive"))
      (node (ref "C15") (pin "1") (pinfunction "1_1") (pintype "passive"))
      (node (ref "C16") (pin "1") (pinfunction "1_1") (pintype "passive"))
      (node (ref "C17") (pin "2") (pinfunction "2_2") (pintype "passive"))
      (node (ref "C18") (pin "2") (pinfunction "2_2") (pintype "passive"))
      (node (ref "C19") (pin "2") (pinfunction "2_2") (pintype "passive"))
      (node (ref "C2") (pin "1") (pinfunction "1_1") (pintype "passive"))
      (node (ref "C20") (pin "1") (pinfunction "1_1") (pintype "passive"))
      (node (ref "C21") (pin "2") (pinfunction "2_2") (pintype "passive"))
      (node (ref "C22") (pin "2") (pinfunction "2_2") (pintype "passive"))
      (node (ref "C23") (pin "1") (pinfunction "1_1") (pintype "passive"))
      (node (ref "C25") (pin "2") (pinfunction "2_2") (pintype "passive"))
      (node (ref "C27") (pin "1") (pinfunction "1_1") (pintype "passive"))
      (node (ref "C28") (pin "2") (pinfunction "2_2") (pintype "passive"))
      (node (ref "C3") (pin "2") (pinfunction "2_2") (pintype "passive"))
      (node (ref "C30") (pin "1") (pinfunction "1_1") (pintype "passive"))
      (node (ref "C33") (pin "2") (pinfunction "2_2") (pintype "passive"))
      (node (ref "C4") (pin "2") (pinfunction "2_2") (pintype "passive"))
      (node (ref "C5") (pin "2") (pinfunction "2_2") (pintype "passive"))
      (node (ref "C8") (pin "2") (pinfunction "2_2") (pintype "passive"))
      (node (ref "C9") (pin "1") (pinfunction "1_1") (pintype "passive"))
      (node (ref "GND") (pin "1") (pinfunction "TestPoint_1") (pintype "passive"))
      (node (ref "IC1") (pin "1") (pinfunction "CLKIN_1") (pintype "passive"))
      (node (ref "IC1") (pin "11") (pinfunction "FSYNC_11") (pintype "passive"))
      (node (ref "IC1") (pin "18") (pinfunction "GND_18") (pintype "passive"))
      (node (ref "IC2") (pin "2") (pinfunction "GND_2") (pintype "passive"))
      (node (ref "POWER1") (pin "2") (pinfunction "2_2") (pintype "passive"))
      (node (ref "Q1") (pin "2") (pinfunction "S_2") (pintype "passive"))
      (node (ref "Q2") (pin "2") (pinfunction "S_2") (pintype "passive"))
      (node (ref "Q3") (pin "2") (pinfunction "S_2") (pintype "passive"))
      (node (ref "Q4") (pin "2") (pinfunction "S_2") (pintype "passive"))
      (node (ref "Q6") (pin "2") (pinfunction "S_2") (pintype "passive"))
      (node (ref "Q7") (pin "2") (pinfunction "S_2") (pintype "passive"))
      (node (ref "R10") (pin "1") (pinfunction "1_1") (pintype "passive"))
      (node (ref "R15") (pin "2") (pinfunction "2_2") (pintype "passive"))
      (node (ref "R19") (pin "2") (pinfunction "2_2") (pintype "passive"))
      (node (ref "R20") (pin "2") (pinfunction "2_2") (pintype "passive"))
      (node (ref "R21") (pin "1") (pinfunction "1_1") (pintype "passive"))
      (node (ref "R22") (pin "1") (pinfunction "1_1") (pintype "passive"))
      (node (ref "R24") (pin "1") (pinfunction "1_1") (pintype "passive"))
      (node (ref "R5") (pin "1") (pinfunction "1_1") (pintype "passive"))
      (node (ref "R6") (pin "2") (pinfunction "2_2") (pintype "passive"))
      (node (ref "R8") (pin "2") (pinfunction "2_2") (pintype "passive"))
      (node (ref "R9") (pin "1") (pinfunction "1_1") (pintype "passive"))
      (node (ref "U1") (pin "23") (pinfunction "VSS_23") (pintype "passive"))
      (node (ref "U1") (pin "35") (pinfunction "VSS_35") (pintype "passive"))
      (node (ref "U1") (pin "47") (pinfunction "VSS_47") (pintype "passive"))
      (node (ref "U1") (pin "49") (pinfunction "PAD_49") (pintype "passive"))
      (node (ref "U1") (pin "8") (pinfunction "VSSA/VREF-_8") (pintype "passive"))
      (node (ref "U2") (pin "12") (pinfunction "GND4_12") (pintype "passive"))
      (node (ref "U2") (pin "2") (pinfunction "VSS_2") (pintype "passive"))
      (node (ref "U2") (pin "3") (pinfunction "GND_3") (pintype "passive"))
      (node (ref "U2") (pin "4") (pinfunction "GND2_4") (pintype "passive"))
      (node (ref "U2") (pin "6") (pinfunction "GND3_6") (pintype "passive"))
      (node (ref "U3") (pin "2") (pinfunction "2_2") (pintype "passive"))
      (node (ref "U3") (pin "5") (pinfunction "5_5") (pintype "passive"))
      (node (ref "U3") (pin "6") (pinfunction "6_6") (pintype "passive"))
      (node (ref "U4") (pin "2") (pinfunction "GND_2") (pintype "passive"))
      (node (ref "U5") (pin "1") (pinfunction "GND_1") (pintype "passive"))
      (node (ref "U5") (pin "7") (pinfunction "GND_7") (pintype "passive"))
      (node (ref "U6") (pin "11") (pinfunction "GND_11") (pintype "passive"))
      (node (ref "U6") (pin "9") (pinfunction "GND_9") (pintype "passive"))
      (node (ref "U7") (pin "10") (pinfunction "GPIO15_10") (pintype "passive"))
      (node (ref "U7") (pin "9") (pinfunction "GND_9") (pintype "passive"))
      (node (ref "port") (pin "2") (pinfunction "2_2") (pintype "passive"))
      (node (ref "port") (pin "5") (pinfunction "5_5") (pintype "passive"))
    )
    (net (code "25") (name "Net-(BUZZER1--)") (class "Default")
      (node (ref "BUZZER1") (pin "3") (pinfunction "-_3") (pintype "passive"))
      (node (ref "Q6") (pin "3") (pinfunction "D_3") (pintype "passive"))
    )
    (net (code "26") (name "Net-(D1-A)") (class "Default")
      (node (ref "C6") (pin "1") (pinfunction "1_1") (pintype "passive"))
      (node (ref "D1") (pin "1") (pinfunction "A_1") (pintype "passive"))
      (node (ref "M2") (pin "2") (pinfunction "2_2") (pintype "passive"))
      (node (ref "Q1") (pin "3") (pinfunction "D_3") (pintype "passive"))
    )
    (net (code "27") (name "Net-(D2-A)") (class "Default")
      (node (ref "C7") (pin "1") (pinfunction "1_1") (pintype "passive"))
      (node (ref "D2") (pin "1") (pinfunction "A_1") (pintype "passive"))
      (node (ref "M1") (pin "2") (pinfunction "2_2") (pintype "passive"))
      (node (ref "Q2") (pin "3") (pinfunction "D_3") (pintype "passive"))
    )
    (net (code "28") (name "Net-(D3-A)") (class "Default")
      (node (ref "C13") (pin "1") (pinfunction "1_1") (pintype "passive"))
      (node (ref "D3") (pin "1") (pinfunction "A_1") (pintype "passive"))
      (node (ref "M3") (pin "2") (pinfunction "2_2") (pintype "passive"))
      (node (ref "Q3") (pin "3") (pinfunction "D_3") (pintype "passive"))
    )
    (net (code "29") (name "Net-(D4-A)") (class "Default")
      (node (ref "C14") (pin "1") (pinfunction "1_1") (pintype "passive"))
      (node (ref "D4") (pin "1") (pinfunction "A_1") (pintype "passive"))
      (node (ref "M4") (pin "2") (pinfunction "2_2") (pintype "passive"))
      (node (ref "Q4") (pin "3") (pinfunction "D_3") (pintype "passive"))
    )
    (net (code "30") (name "Net-(D5-A)") (class "Default")
      (node (ref "D5") (pin "1") (pinfunction "A_1") (pintype "passive"))
      (node (ref "IC2") (pin "1") (pinfunction "SW_1") (pintype "passive"))
      (node (ref "L1") (pin "2") (pinfunction "2_2") (pintype "passive"))
    )
    (net (code "31") (name "Net-(IC1-AD0)") (class "Default")
      (node (ref "IC1") (pin "9") (pinfunction "AD0_9") (pintype "passive"))
      (node (ref "R5") (pin "2") (pinfunction "2_2") (pintype "passive"))
    )
    (net (code "32") (name "Net-(IC1-CPOUT)") (class "Default")
      (node (ref "C1") (pin "1") (pinfunction "1_1") (pintype "passive"))
      (node (ref "IC1") (pin "20") (pinfunction "CPOUT_20") (pintype "passive"))
    )
    (net (code "33") (name "Net-(IC1-REGOUT)") (class "Default")
      (node (ref "C3") (pin "1") (pinfunction "1_1") (pintype "passive"))
      (node (ref "IC1") (pin "10") (pinfunction "REGOUT_10") (pintype "passive"))
    )
    (net (code "34") (name "Net-(IC2-EN)") (class "Default")
      (node (ref "IC2") (pin "4") (pinfunction "EN_4") (pintype "passive"))
      (node (ref "R7") (pin "2") (pinfunction "2_2") (pintype "passive"))
    )
    (net (code "35") (name "Net-(IC2-FB)") (class "Default")
      (node (ref "C26") (pin "2") (pinfunction "2_2") (pintype "passive"))
      (node (ref "IC2") (pin "3") (pinfunction "FB_3") (pintype "passive"))
      (node (ref "R11") (pin "1") (pinfunction "1_1") (pintype "passive"))
      (node (ref "R15") (pin "1") (pinfunction "1_1") (pintype "passive"))
    )
    (net (code "36") (name "Net-(LED2-K)") (class "Default")
      (node (ref "LED2") (pin "1") (pinfunction "K_1") (pintype "passive"))
      (node (ref "Q7") (pin "3") (pinfunction "D_3") (pintype "passive"))
    )
    (net (code "37") (name "Net-(POWER1-Pad1)") (class "Default")
      (node (ref "POWER1") (pin "1") (pinfunction "1_1") (pintype "passive"))
      (node (ref "S1") (pin "2") (pintype "passive"))
    )
    (net (code "38") (name "Net-(Q6-G)") (class "Default")
      (node (ref "Q6") (pin "1") (pinfunction "G_1") (pintype "passive"))
      (node (ref "R4") (pin "1") (pinfunction "1_1") (pintype "passive"))
    )
    (net (code "39") (name "Net-(U1-BOOT0)") (class "Default")
      (node (ref "R10") (pin "2") (pinfunction "2_2") (pintype "passive"))
      (node (ref "U1") (pin "44") (pinfunction "BOOT0_44") (pintype "passive"))
    )
    (net (code "40") (name "Net-(U1-PH0-OSC_IN)") (class "Default")
      (node (ref "C9") (pin "2") (pinfunction "2_2") (pintype "passive"))
      (node (ref "U1") (pin "5") (pinfunction "PH0-OSC_IN_5") (pintype "passive"))
      (node (ref "Y1") (pin "2") (pinfunction "OSC2_2") (pintype "passive"))
    )
    (net (code "41") (name "Net-(U1-PH1-OSC_OUT)") (class "Default")
      (node (ref "C10") (pin "2") (pinfunction "2_2") (pintype "passive"))
      (node (ref "U1") (pin "6") (pinfunction "PH1-OSC_OUT_6") (pintype "passive"))
      (node (ref "Y1") (pin "1") (pinfunction "OSC1_1") (pintype "passive"))
    )
    (net (code "42") (name "Net-(U1-VCAP1)") (class "Default")
      (node (ref "C18") (pin "1") (pinfunction "1_1") (pintype "passive"))
      (node (ref "U1") (pin "22") (pinfunction "VCAP1_22") (pintype "passive"))
    )
    (net (code "43") (name "Net-(U2-GP1)") (class "Default")
      (node (ref "R14") (pin "2") (pinfunction "2_2") (pintype "passive"))
      (node (ref "U2") (pin "7") (pinfunction "GP1_7") (pintype "passive"))
    )
    (net (code "44") (name "Net-(U4-EN)") (class "Default")
      (node (ref "R18") (pin "2") (pinfunction "2_2") (pintype "passive"))
      (node (ref "U4") (pin "1") (pinfunction "EN_1") (pintype "passive"))
    )
    (net (code "45") (name "Net-(U4-FB)") (class "Default")
      (node (ref "C29") (pin "2") (pinfunction "2_2") (pintype "passive"))
      (node (ref "R23") (pin "1") (pinfunction "1_1") (pintype "passive"))
      (node (ref "R24") (pin "2") (pinfunction "2_2") (pintype "passive"))
      (node (ref "U4") (pin "5") (pinfunction "FB_5") (pintype "passive"))
    )
    (net (code "46") (name "Net-(U4-SW)") (class "Default")
      (node (ref "L2") (pin "1") (pinfunction "1_1") (pintype "passive"))
      (node (ref "U4") (pin "3") (pinfunction "SW_3") (pintype "passive"))
    )
    (net (code "47") (name "Net-(U6-C1)") (class "Default")
      (node (ref "C23") (pin "2") (pinfunction "2_2") (pintype "passive"))
      (node (ref "U6") (pin "10") (pinfunction "C1_10") (pintype "passive"))
    )
    (net (code "48") (name "Net-(U6-SETC)") (class "Default")
      (node (ref "C24") (pin "1") (pinfunction "1_1") (pintype "passive"))
      (node (ref "U6") (pin "12") (pinfunction "SETC_12") (pintype "passive"))
    )
    (net (code "49") (name "Net-(U6-SETP)") (class "Default")
      (node (ref "C24") (pin "2") (pinfunction "2_2") (pintype "passive"))
      (node (ref "U6") (pin "8") (pinfunction "SETP_8") (pintype "passive"))
    )
    (net (code "50") (name "Net-(U7-EN)") (class "Default")
      (node (ref "R16") (pin "2") (pinfunction "2_2") (pintype "passive"))
      (node (ref "U7") (pin "3") (pinfunction "EN_3") (pintype "passive"))
    )
    (net (code "51") (name "VCC") (class "Default")
      (node (ref "BUZZER1") (pin "2") (pinfunction "+_2") (pintype "passive"))
      (node (ref "C13") (pin "2") (pinfunction "2_2") (pintype "passive"))
      (node (ref "C14") (pin "2") (pinfunction "2_2") (pintype "passive"))
      (node (ref "C19") (pin "1") (pinfunction "1_1") (pintype "passive"))
      (node (ref "C6") (pin "2") (pinfunction "2_2") (pintype "passive"))
      (node (ref "C7") (pin "2") (pinfunction "2_2") (pintype "passive"))
      (node (ref "D1") (pin "2") (pinfunction "K_2") (pintype "passive"))
      (node (ref "D2") (pin "2") (pinfunction "K_2") (pintype "passive"))
      (node (ref "D3") (pin "2") (pinfunction "K_2") (pintype "passive"))
      (node (ref "D4") (pin "2") (pinfunction "K_2") (pintype "passive"))
      (node (ref "IC2") (pin "5") (pinfunction "IN_5") (pintype "passive"))
      (node (ref "L1") (pin "1") (pinfunction "1_1") (pintype "passive"))
      (node (ref "LED2") (pin "2") (pinfunction "A_2") (pintype "passive"))
      (node (ref "M1") (pin "1") (pinfunction "1_1") (pintype "passive"))
      (node (ref "M2") (pin "1") (pinfunction "1_1") (pintype "passive"))
      (node (ref "M3") (pin "1") (pinfunction "1_1") (pintype "passive"))
      (node (ref "M4") (pin "1") (pinfunction "1_1") (pintype "passive"))
      (node (ref "R3") (pin "1") (pinfunction "1_1") (pintype "passive"))
      (node (ref "R7") (pin "1") (pinfunction "1_1") (pintype "passive"))
      (node (ref "S1") (pin "1") (pintype "passive"))
      (node (ref "port") (pin "1") (pinfunction "1_1") (pintype "passive"))
    )
    (net (code "52") (name "unconnected-(BUZZER1-NC-Pad1)") (class "Default")
      (node (ref "BUZZER1") (pin "1") (pinfunction "NC_1") (pintype "passive"))
    )
    (net (code "53") (name "unconnected-(IC1-AUXDA-Pad6)") (class "Default")
      (node (ref "IC1") (pin "6") (pinfunction "AUXDA_6") (pintype "passive+no_connect"))
    )
    (net (code "54") (name "unconnected-(IC1-AUXDL-Pad7)") (class "Default")
      (node (ref "IC1") (pin "7") (pinfunction "AUXDL_7") (pintype "passive+no_connect"))
    )
    (net (code "55") (name "unconnected-(IC1-INT-Pad12)") (class "Default")
      (node (ref "IC1") (pin "12") (pinfunction "INT_12") (pintype "passive"))
    )
    (net (code "56") (name "unconnected-(IC1-NC-Pad2)") (class "Default")
      (node (ref "IC1") (pin "2") (pinfunction "NC_2") (pintype "passive+no_connect"))
    )
    (net (code "57") (name "unconnected-(IC1-NC-Pad3)") (class "Default")
      (node (ref "IC1") (pin "3") (pinfunction "NC_3") (pintype "passive+no_connect"))
    )
    (net (code "58") (name "unconnected-(IC1-NC-Pad4)") (class "Default")
      (node (ref "IC1") (pin "4") (pinfunction "NC_4") (pintype "passive+no_connect"))
    )
    (net (code "59") (name "unconnected-(IC1-NC-Pad5)") (class "Default")
      (node (ref "IC1") (pin "5") (pinfunction "NC_5") (pintype "passive+no_connect"))
    )
    (net (code "60") (name "unconnected-(IC1-NC-Pad14)") (class "Default")
      (node (ref "IC1") (pin "14") (pinfunction "NC_14") (pintype "passive+no_connect"))
    )
    (net (code "61") (name "unconnected-(IC1-NC-Pad15)") (class "Default")
      (node (ref "IC1") (pin "15") (pinfunction "NC_15") (pintype "passive+no_connect"))
    )
    (net (code "62") (name "unconnected-(IC1-NC-Pad16)") (class "Default")
      (node (ref "IC1") (pin "16") (pinfunction "NC_16") (pintype "passive+no_connect"))
    )
    (net (code "63") (name "unconnected-(IC1-NC-Pad17)") (class "Default")
      (node (ref "IC1") (pin "17") (pinfunction "NC_17") (pintype "passive+no_connect"))
    )
    (net (code "64") (name "unconnected-(IC1-RESV-Pad19)") (class "Default")
      (node (ref "IC1") (pin "19") (pinfunction "RESV_19") (pintype "passive+no_connect"))
    )
    (net (code "65") (name "unconnected-(IC1-RESV-Pad21)") (class "Default")
      (node (ref "IC1") (pin "21") (pinfunction "RESV_21") (pintype "passive+no_connect"))
    )
    (net (code "66") (name "unconnected-(IC1-RESV-Pad22)") (class "Default")
      (node (ref "IC1") (pin "22") (pinfunction "RESV_22") (pintype "passive+no_connect"))
    )
    (net (code "67") (name "unconnected-(IC2-NC-Pad6)") (class "Default")
      (node (ref "IC2") (pin "6") (pinfunction "NC_6") (pintype "passive+no_connect"))
    )
    (net (code "68") (name "unconnected-(S1-Pad3)") (class "Default")
      (node (ref "S1") (pin "3") (pintype "passive"))
    )
    (net (code "69") (name "unconnected-(U1-NRST-Pad7)") (class "Default")
      (node (ref "U1") (pin "7") (pinfunction "NRST_7") (pintype "passive"))
    )
    (net (code "70") (name "unconnected-(U1-PA1-Pad11)") (class "Default")
      (node (ref "U1") (pin "11") (pinfunction "PA1_11") (pintype "passive"))
    )
    (net (code "71") (name "unconnected-(U1-PA4-Pad14)") (class "Default")
      (node (ref "U1") (pin "14") (pinfunction "PA4_14") (pintype "passive"))
    )
    (net (code "72") (name "unconnected-(U1-PA9-Pad30)") (class "Default")
      (node (ref "U1") (pin "30") (pinfunction "PA9_30") (pintype "passive"))
    )
    (net (code "73") (name "unconnected-(U1-PA15-Pad38)") (class "Default")
      (node (ref "U1") (pin "38") (pinfunction "PA15_38") (pintype "passive"))
    )
    (net (code "74") (name "unconnected-(U1-PB2-Pad20)") (class "Default")
      (node (ref "U1") (pin "20") (pinfunction "PB2_20") (pintype "passive"))
    )
    (net (code "75") (name "unconnected-(U1-PB3-Pad39)") (class "Default")
      (node (ref "U1") (pin "39") (pinfunction "PB3_39") (pintype "passive"))
    )
    (net (code "76") (name "unconnected-(U1-PB4-Pad40)") (class "Default")
      (node (ref "U1") (pin "40") (pinfunction "PB4_40") (pintype "passive"))
    )
    (net (code "77") (name "unconnected-(U1-PB10-Pad21)") (class "Default")
      (node (ref "U1") (pin "21") (pinfunction "PB10_21") (pintype "passive"))
    )
    (net (code "78") (name "unconnected-(U1-PB14-Pad27)") (class "Default")
      (node (ref "U1") (pin "27") (pinfunction "PB14_27") (pintype "passive"))
    )
    (net (code "79") (name "unconnected-(U1-PB15-Pad28)") (class "Default")
      (node (ref "U1") (pin "28") (pinfunction "PB15_28") (pintype "passive"))
    )
    (net (code "80") (name "unconnected-(U1-PC13-Pad2)") (class "Default")
      (node (ref "U1") (pin "2") (pinfunction "PC13_2") (pintype "passive"))
    )
    (net (code "81") (name "unconnected-(U1-PC14{slash}OSC32IN-Pad3)") (class "Default")
      (node (ref "U1") (pin "3") (pinfunction "PC14/OSC32IN_3") (pintype "passive"))
    )
    (net (code "82") (name "unconnected-(U1-PC15{slash}OSC32OUT-Pad4)") (class "Default")
      (node (ref "U1") (pin "4") (pinfunction "PC15/OSC32OUT_4") (pintype "passive"))
    )
    (net (code "83") (name "unconnected-(U2-DNC-Pad8)") (class "Default")
      (node (ref "U2") (pin "8") (pinfunction "DNC_8") (pintype "passive"))
    )
    (net (code "84") (name "unconnected-(U5-CSB-Pad2)") (class "Default")
      (node (ref "U5") (pin "2") (pinfunction "CSB_2") (pintype "passive"))
    )
    (net (code "85") (name "unconnected-(U5-SDO-Pad5)") (class "Default")
      (node (ref "U5") (pin "5") (pinfunction "SDO_5") (pintype "passive"))
    )
    (net (code "86") (name "unconnected-(U6-DRDY-Pad15)") (class "Default")
      (node (ref "U6") (pin "15") (pinfunction "DRDY_15") (pintype "passive"))
    )
    (net (code "87") (name "unconnected-(U6-NC-Pad3)") (class "Default")
      (node (ref "U6") (pin "3") (pinfunction "NC_3") (pintype "passive"))
    )
    (net (code "88") (name "unconnected-(U6-NC-Pad5)") (class "Default")
      (node (ref "U6") (pin "5") (pinfunction "NC_5") (pintype "passive"))
    )
    (net (code "89") (name "unconnected-(U6-NC-Pad6)") (class "Default")
      (node (ref "U6") (pin "6") (pinfunction "NC_6") (pintype "passive"))
    )
    (net (code "90") (name "unconnected-(U6-NC-Pad7)") (class "Default")
      (node (ref "U6") (pin "7") (pinfunction "NC_7") (pintype "passive"))
    )
    (net (code "91") (name "unconnected-(U6-NC-Pad14)") (class "Default")
      (node (ref "U6") (pin "14") (pinfunction "NC_14") (pintype "passive"))
    )
    (net (code "92") (name "unconnected-(U7-ADC-Pad2)") (class "Default")
      (node (ref "U7") (pin "2") (pinfunction "ADC_2") (pintype "passive"))
    )
    (net (code "93") (name "unconnected-(U7-CS0-Pad17)") (class "Default")
      (node (ref "U7") (pin "17") (pinfunction "CS0_17") (pintype "passive"))
    )
    (net (code "94") (name "unconnected-(U7-GPIO4-Pad13)") (class "Default")
      (node (ref "U7") (pin "13") (pinfunction "GPIO4_13") (pintype "passive"))
    )
    (net (code "95") (name "unconnected-(U7-GPIO5-Pad14)") (class "Default")
      (node (ref "U7") (pin "14") (pinfunction "GPIO5_14") (pintype "passive"))
    )
    (net (code "96") (name "unconnected-(U7-GPIO9-Pad19)") (class "Default")
      (node (ref "U7") (pin "19") (pinfunction "GPIO9_19") (pintype "passive"))
    )
    (net (code "97") (name "unconnected-(U7-GPIO10-Pad20)") (class "Default")
      (node (ref "U7") (pin "20") (pinfunction "GPIO10_20") (pintype "passive"))
    )
    (net (code "98") (name "unconnected-(U7-GPIO12-Pad6)") (class "Default")
      (node (ref "U7") (pin "6") (pinfunction "GPIO12_6") (pintype "passive"))
    )
    (net (code "99") (name "unconnected-(U7-GPIO13-Pad7)") (class "Default")
      (node (ref "U7") (pin "7") (pinfunction "GPIO13_7") (pintype "passive"))
    )
    (net (code "100") (name "unconnected-(U7-GPIO14-Pad5)") (class "Default")
      (node (ref "U7") (pin "5") (pinfunction "GPIO14_5") (pintype "passive"))
    )
    (net (code "101") (name "unconnected-(U7-GPIO16-Pad4)") (class "Default")
      (node (ref "U7") (pin "4") (pinfunction "GPIO16_4") (pintype "passive"))
    )
    (net (code "102") (name "unconnected-(U7-MISO-Pad18)") (class "Default")
      (node (ref "U7") (pin "18") (pinfunction "MISO_18") (pintype "passive"))
    )
    (net (code "103") (name "unconnected-(U7-MOSI-Pad21)") (class "Default")
      (node (ref "U7") (pin "21") (pinfunction "MOSI_21") (pintype "passive"))
    )
    (net (code "104") (name "unconnected-(U7-SCLK-Pad22)") (class "Default")
      (node (ref "U7") (pin "22") (pinfunction "SCLK_22") (pintype "passive"))
    )
  )
)
